# ADC_Connector.net
KiCad netlist of a schematic drawn in Altium Designer
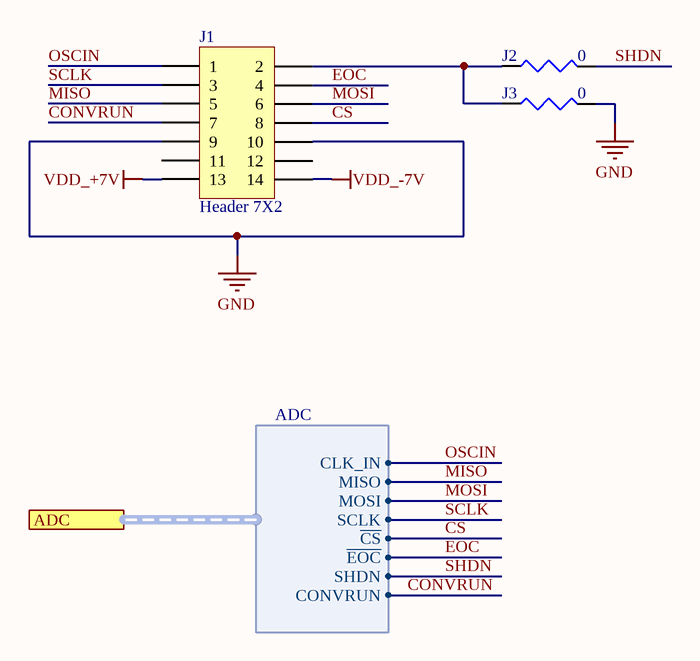
[diagram p0: ADC_Connector.SchDoc]

(export (version "E")
  (design (tool "Eeschema 10.0.6"))
  (components
    (comp (ref "J1")
      (value "Header 7X2")
      (footprint "FLE-107-01-G-DV-A-TR")
      (description "Header, 7-Pin, Dual row")
      (fields (field (name "PUBLISHER") "Altium Limited"))
      (libsource (lib "Miscellaneous Connectors") (part "Header 7X2"))
    )
    (comp (ref "J2")
      (value "0")
      (footprint "J1-0603")
      (description "Resistor")
      (fields (field (name "Comment") "Res3") (field (name "PUBLISHER") "Altium Limited"))
      (libsource (lib "Miscellaneous Devices") (part "Res3"))
    )
    (comp (ref "J3")
      (value "0")
      (footprint "J1-0603")
      (description "Resistor")
      (fields (field (name "Comment") "Res3") (field (name "PUBLISHER") "Altium Limited"))
      (libsource (lib "Miscellaneous Devices") (part "Res3"))
    )
  )
  (nets
    (net (code "2") (name "/CONVRUN") (class "Default")
      (node (ref "J1") (pin "7") (pinfunction "7_7") (pintype "passive"))
    )
    (net (code "3") (name "/MISO") (class "Default")
      (node (ref "J1") (pin "5") (pinfunction "5_5") (pintype "passive"))
    )
    (net (code "4") (name "/MOSI") (class "Default")
      (node (ref "J1") (pin "6") (pinfunction "6_6") (pintype "passive"))
    )
    (net (code "5") (name "/OSCIN") (class "Default")
      (node (ref "J1") (pin "1") (pinfunction "1_1") (pintype "passive"))
    )
    (net (code "6") (name "/SCLK") (class "Default")
      (node (ref "J1") (pin "3") (pinfunction "3_3") (pintype "passive"))
    )
    (net (code "7") (name "/SHDN") (class "Default")
      (node (ref "J2") (pin "2") (pinfunction "2_2") (pintype "passive"))
    )
    (net (code "9") (name "/~{CS}") (class "Default")
      (node (ref "J1") (pin "8") (pinfunction "8_8") (pintype "passive"))
    )
    (net (code "10") (name "/~{EOC}") (class "Default")
      (node (ref "J1") (pin "4") (pinfunction "4_4") (pintype "passive"))
    )
    (net (code "11") (name "GND") (class "Default")
      (node (ref "J1") (pin "10") (pinfunction "10_10") (pintype "passive"))
      (node (ref "J1") (pin "9") (pinfunction "9_9") (pintype "passive"))
      (node (ref "J3") (pin "2") (pinfunction "2_2") (pintype "passive"))
    )
    (net (code "12") (name "Net-(J1-Pad2)") (class "Default")
      (node (ref "J1") (pin "2") (pinfunction "2_2") (pintype "passive"))
      (node (ref "J2") (pin "1") (pinfunction "1_1") (pintype "passive"))
      (node (ref "J3") (pin "1") (pinfunction "1_1") (pintype "passive"))
    )
    (net (code "13") (name "VDD_+7V") (class "Default")
      (node (ref "J1") (pin "13") (pinfunction "13_13") (pintype "passive"))
    )
    (net (code "14") (name "VDD_-7V") (class "Default")
      (node (ref "J1") (pin "14") (pinfunction "14_14") (pintype "passive"))
    )
    (net (code "15") (name "unconnected-(J1-Pad11)") (class "Default")
      (node (ref "J1") (pin "11") (pinfunction "11_11") (pintype "passive"))
    )
    (net (code "16") (name "unconnected-(J1-Pad12)") (class "Default")
      (node (ref "J1") (pin "12") (pinfunction "12_12") (pintype "passive"))
    )
  )
)
